# Light.net
KiCad netlist of a schematic drawn in EAGLE
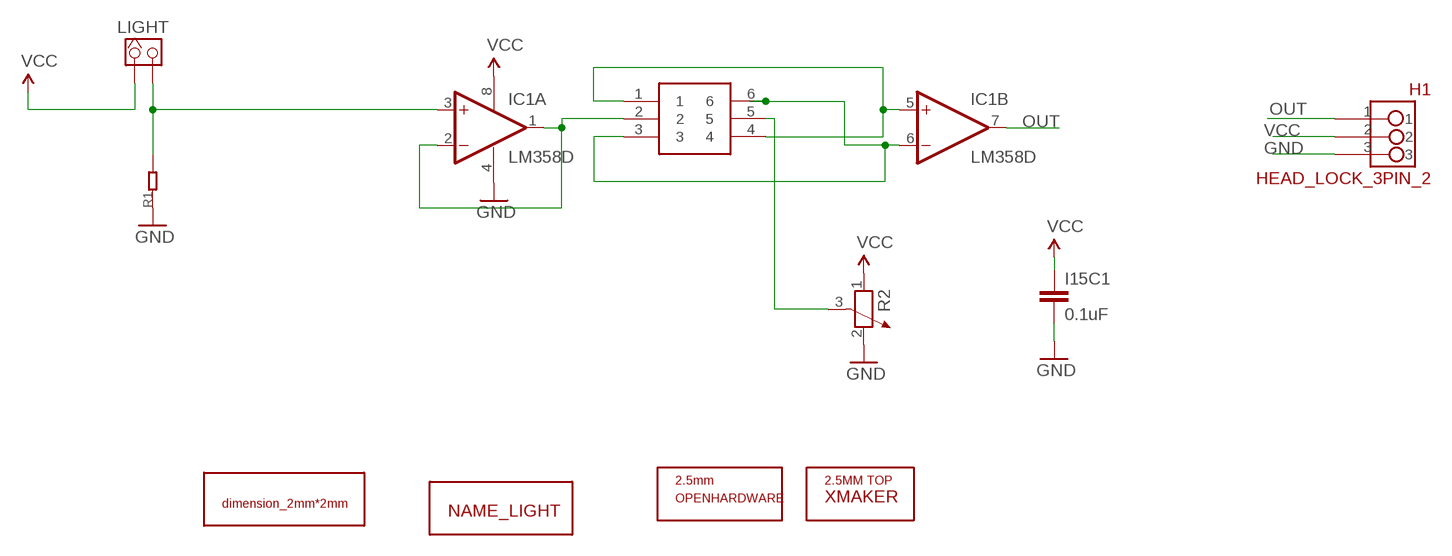
[diagram p0: schematic, sheet 1]

(export (version "E")
  (design (tool "Eeschema 10.0.6"))
  (components
    (comp (ref "H1")
      (value "HEAD_LOCK_3PIN_2")
      (footprint "eagle-import:HEAD_LOCK_3PIN_2")
      (libsource (lib "eagle-import") (part "HEAD_LOCK_3PIN_2"))
    )
    (comp (ref "I15C1")
      (value "0.1uF")
      (footprint "eagle-import:0603-CAP")
      (libsource (lib "eagle-import") (part "CAP0603-CAP"))
    )
    (comp (ref "IC1")
      (value "LM358D")
      (footprint "eagle-import:SO08")
      (libsource (lib "eagle-import") (part "LM358D"))
    )
    (comp (ref "LIGHT")
      (value "HEADER_1X2_2.54")
      (footprint "eagle-import:CK_1_2")
      (libsource (lib "eagle-import") (part "HEADER_1X2_2.54"))
    )
    (comp (ref "R1")
      (value "R0603")
      (footprint "eagle-import:0603")
      (libsource (lib "eagle-import") (part "R0603"))
    )
    (comp (ref "R2")
      (value "R-POTENTIOMETER3362")
      (footprint "eagle-import:3P-SQUA-7X6.8")
      (libsource (lib "eagle-import") (part "R-POTENTIOMETER3362"))
    )
    (comp (ref "U$1")
      (value "DIMENSION_2MM2MM")
      (footprint "eagle-import:DIMENSION_2MM_2MM")
      (libsource (lib "eagle-import") (part "DIMENSION_2MM2MM"))
    )
    (comp (ref "U$2")
      (value "NAME_LIGHT")
      (footprint "eagle-import:NAME_LIGHT")
      (libsource (lib "eagle-import") (part "NAME_LIGHT"))
    )
    (comp (ref "U$3")
      (value "OPENHARDWARE_2.5MM_TOP")
      (footprint "eagle-import:OPENSOURCELOGO_2.5MM")
      (libsource (lib "eagle-import") (part "OPENHARDWARE_2.5MM_TOP"))
    )
    (comp (ref "U$4")
      (value "XMAKERLOGO_2.5MM_TOP")
      (footprint "eagle-import:XMAKERLOGO_2.5MM_TOP")
      (libsource (lib "eagle-import") (part "XMAKERLOGO_2.5MM_TOP"))
    )
    (comp (ref "U$5")
      (value "MSS-22C02")
      (footprint "eagle-import:MSS-22C02")
      (libsource (lib "eagle-import") (part "MSS-22C02"))
    )
  )
  (nets
    (net (code "1") (name "/OUT") (class "Default")
      (node (ref "H1") (pin "1") (pinfunction "1_1") (pintype "passive"))
      (node (ref "IC1") (pin "7") (pinfunction "OUT_7") (pintype "output"))
    )
    (net (code "2") (name "GND") (class "Default")
      (node (ref "H1") (pin "3") (pinfunction "3_3") (pintype "passive"))
      (node (ref "I15C1") (pin "2") (pinfunction "2_2") (pintype "passive"))
      (node (ref "IC1") (pin "4") (pinfunction "V-_4") (pintype "power_in"))
      (node (ref "R1") (pin "1") (pinfunction "1_1") (pintype "bidirectional"))
      (node (ref "R2") (pin "2") (pinfunction "2_2") (pintype "passive"))
    )
    (net (code "3") (name "Net-(IC1A-+IN)") (class "Default")
      (node (ref "IC1") (pin "3") (pinfunction "+IN_3") (pintype "input"))
      (node (ref "LIGHT") (pin "2") (pinfunction "2_2") (pintype "bidirectional"))
      (node (ref "R1") (pin "2") (pinfunction "2_2") (pintype "bidirectional"))
    )
    (net (code "4") (name "Net-(IC1A--IN)") (class "Default")
      (node (ref "IC1") (pin "1") (pinfunction "OUT_1") (pintype "output"))
      (node (ref "IC1") (pin "2") (pinfunction "-IN_2") (pintype "input"))
      (node (ref "U$5") (pin "2") (pinfunction "2_2") (pintype "bidirectional"))
    )
    (net (code "5") (name "Net-(IC1B-+IN)") (class "Default")
      (node (ref "IC1") (pin "5") (pinfunction "+IN_5") (pintype "input"))
      (node (ref "U$5") (pin "1") (pinfunction "1_1") (pintype "bidirectional"))
      (node (ref "U$5") (pin "4") (pinfunction "4_4") (pintype "bidirectional"))
    )
    (net (code "6") (name "Net-(IC1B--IN)") (class "Default")
      (node (ref "IC1") (pin "6") (pinfunction "-IN_6") (pintype "input"))
      (node (ref "U$5") (pin "3") (pinfunction "3_3") (pintype "bidirectional"))
      (node (ref "U$5") (pin "6") (pinfunction "6_6") (pintype "bidirectional"))
    )
    (net (code "7") (name "Net-(R2-Pad3)") (class "Default")
      (node (ref "R2") (pin "3") (pinfunction "3_3") (pintype "passive"))
      (node (ref "U$5") (pin "5") (pinfunction "5_5") (pintype "bidirectional"))
    )
    (net (code "8") (name "VCC") (class "Default")
      (node (ref "H1") (pin "2") (pinfunction "2_2") (pintype "passive"))
      (node (ref "I15C1") (pin "1") (pinfunction "1_1") (pintype "passive"))
      (node (ref "IC1") (pin "8") (pinfunction "V+_8") (pintype "power_in"))
      (node (ref "LIGHT") (pin "1") (pinfunction "1_1") (pintype "bidirectional"))
      (node (ref "R2") (pin "1") (pinfunction "1_1") (pintype "passive"))
    )
  )
)
